# IR_Sync_Emitter_with_sensor.net
KiCad netlist of a schematic drawn in EAGLE
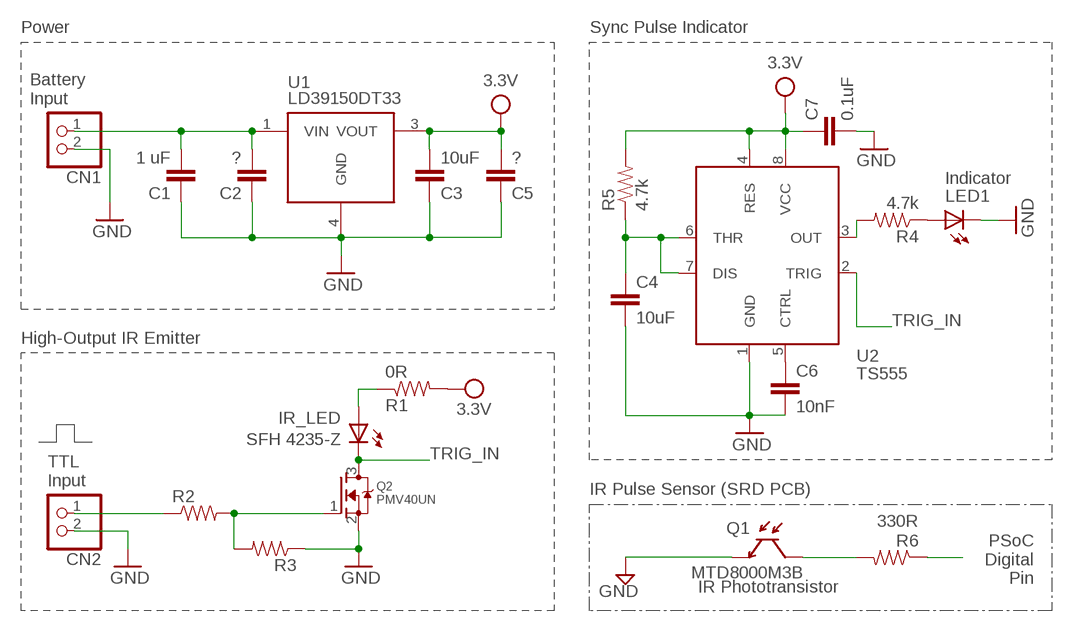
[diagram p0: schematic, sheet 1]

(export (version "E")
  (design (tool "Eeschema 10.0.6"))
  (components
    (comp (ref "C1")
      (value "1 uF")
      (footprint "eagle-import:CAPC2012X100N")
      (libsource (lib "eagle-import") (part "CC0805-N"))
    )
    (comp (ref "C2")
      (value "?")
      (footprint "eagle-import:CAPC2012X100N")
      (libsource (lib "eagle-import") (part "CC0805-N"))
    )
    (comp (ref "C3")
      (value "10uF")
      (footprint "eagle-import:CAPC2012X100N")
      (libsource (lib "eagle-import") (part "CC0805-N"))
    )
    (comp (ref "C4")
      (value "10uF")
      (footprint "eagle-import:CAPC2012X100N")
      (libsource (lib "eagle-import") (part "CC0805-N"))
    )
    (comp (ref "C5")
      (value "?")
      (footprint "eagle-import:CAPC2012X100N")
      (libsource (lib "eagle-import") (part "CC0805-N"))
    )
    (comp (ref "C6")
      (value "10nF")
      (footprint "eagle-import:CAPC2012X100N")
      (libsource (lib "eagle-import") (part "CC0805-N"))
    )
    (comp (ref "C7")
      (value "0.1uF")
      (footprint "eagle-import:CAPC2012X100N")
      (libsource (lib "eagle-import") (part "CC0805-N"))
    )
    (comp (ref "CN1")
      (value "JST_2PIN-SMT-RA")
      (footprint "eagle-import:JST-PH-2-SMT-RA")
      (libsource (lib "eagle-import") (part "JST_2PIN-SMT-RA"))
    )
    (comp (ref "CN2")
      (value "JST_2PIN-SMT-RA")
      (footprint "eagle-import:JST-PH-2-SMT-RA")
      (libsource (lib "eagle-import") (part "JST_2PIN-SMT-RA"))
    )
    (comp (ref "IR_LED")
      (value "LEDIR_SMT16.2X11.2")
      (footprint "eagle-import:LED_SMT6.2X11.2")
      (libsource (lib "eagle-import") (part "LEDIR_SMT16.2X11.2"))
    )
    (comp (ref "LED1")
      (value "LED0603")
      (footprint "eagle-import:CHIPLED_0603")
      (libsource (lib "eagle-import") (part "LED0603"))
    )
    (comp (ref "Q1")
      (value "MTD8000M3B")
      (footprint "eagle-import:MTD8000M3B-T")
      (libsource (lib "eagle-import") (part "PHOTOTRANSISTOR"))
    )
    (comp (ref "Q2")
      (value "PMV40UN")
      (footprint "eagle-import:SOT23")
      (libsource (lib "eagle-import") (part "MOSFET-NREFLOW"))
    )
    (comp (ref "R1")
      (value "0R")
      (footprint "eagle-import:RESC3116X65N")
      (libsource (lib "eagle-import") (part "RR1206-N"))
    )
    (comp (ref "R2")
      (value "RR0805-N")
      (footprint "eagle-import:RESC2012X60N")
      (libsource (lib "eagle-import") (part "RR0805-N"))
    )
    (comp (ref "R3")
      (value "RR0805-N")
      (footprint "eagle-import:RESC2012X60N")
      (libsource (lib "eagle-import") (part "RR0805-N"))
    )
    (comp (ref "R4")
      (value "4.7k")
      (footprint "eagle-import:RESC2012X60N")
      (libsource (lib "eagle-import") (part "RR0805-N"))
    )
    (comp (ref "R5")
      (value "4.7k")
      (footprint "eagle-import:RESC2012X60N")
      (libsource (lib "eagle-import") (part "RR0805-N"))
    )
    (comp (ref "R6")
      (value "330R")
      (footprint "eagle-import:RESC2012X60N")
      (libsource (lib "eagle-import") (part "RR0805-N"))
    )
    (comp (ref "U1")
      (value "LM2931_FIXED")
      (footprint "eagle-import:DPAK")
      (libsource (lib "eagle-import") (part "LM2931_FIXED"))
    )
    (comp (ref "U2")
      (value "TS555")
      (footprint "eagle-import:SO08")
      (libsource (lib "eagle-import") (part "TS555"))
    )
  )
  (nets
    (net (code "1") (name "/TRIG_IN") (class "Default")
      (node (ref "IR_LED") (pin "C") (pinfunction "C_C") (pintype "passive"))
      (node (ref "Q2") (pin "3") (pinfunction "D_3") (pintype "bidirectional"))
      (node (ref "U2") (pin "2") (pinfunction "TRIG_2") (pintype "bidirectional"))
    )
    (net (code "2") (name "GND") (class "Default")
      (node (ref "C1") (pin "1") (pinfunction "1_1") (pintype "passive"))
      (node (ref "C2") (pin "1") (pinfunction "1_1") (pintype "passive"))
      (node (ref "C3") (pin "1") (pinfunction "1_1") (pintype "passive"))
      (node (ref "C4") (pin "2") (pinfunction "2_2") (pintype "passive"))
      (node (ref "C5") (pin "1") (pinfunction "1_1") (pintype "passive"))
      (node (ref "C6") (pin "2") (pinfunction "2_2") (pintype "passive"))
      (node (ref "C7") (pin "2") (pinfunction "2_2") (pintype "passive"))
      (node (ref "CN1") (pin "2") (pinfunction "1_2") (pintype "passive"))
      (node (ref "CN2") (pin "2") (pinfunction "1_2") (pintype "passive"))
      (node (ref "LED1") (pin "C") (pinfunction "C_C") (pintype "passive"))
      (node (ref "Q1") (pin "E") (pinfunction "E_E") (pintype "bidirectional"))
      (node (ref "Q2") (pin "2") (pinfunction "S_2") (pintype "bidirectional"))
      (node (ref "R3") (pin "1") (pinfunction "1_1") (pintype "passive"))
      (node (ref "U1") (pin "4") (pinfunction "GND_4") (pintype "bidirectional"))
      (node (ref "U2") (pin "1") (pinfunction "GND_1") (pintype "power_in"))
    )
    (net (code "3") (name "Net-(CN1-2)") (class "Default")
      (node (ref "C1") (pin "2") (pinfunction "2_2") (pintype "passive"))
      (node (ref "C2") (pin "2") (pinfunction "2_2") (pintype "passive"))
      (node (ref "CN1") (pin "1") (pinfunction "2_1") (pintype "passive"))
      (node (ref "U1") (pin "1") (pinfunction "VIN_1") (pintype "bidirectional"))
    )
    (net (code "4") (name "Net-(CN2-2)") (class "Default")
      (node (ref "CN2") (pin "1") (pinfunction "2_1") (pintype "passive"))
      (node (ref "R2") (pin "1") (pinfunction "1_1") (pintype "passive"))
    )
    (net (code "5") (name "Net-(IR_LED-PadA)") (class "Default")
      (node (ref "IR_LED") (pin "A") (pinfunction "A_A") (pintype "passive"))
      (node (ref "R1") (pin "1") (pinfunction "1_1") (pintype "passive"))
    )
    (net (code "6") (name "Net-(LED1-PadA)") (class "Default")
      (node (ref "LED1") (pin "A") (pinfunction "A_A") (pintype "passive"))
      (node (ref "R4") (pin "1") (pinfunction "1_1") (pintype "passive"))
    )
    (net (code "7") (name "Net-(Q1-PadC)") (class "Default")
      (node (ref "Q1") (pin "C") (pinfunction "C_C") (pintype "bidirectional"))
      (node (ref "R6") (pin "2") (pinfunction "2_2") (pintype "passive"))
    )
    (net (code "8") (name "Net-(Q2-G)") (class "Default")
      (node (ref "Q2") (pin "1") (pinfunction "G_1") (pintype "bidirectional"))
      (node (ref "R2") (pin "2") (pinfunction "2_2") (pintype "passive"))
      (node (ref "R3") (pin "2") (pinfunction "2_2") (pintype "passive"))
    )
    (net (code "9") (name "Net-(U2-CTRL)") (class "Default")
      (node (ref "C6") (pin "1") (pinfunction "1_1") (pintype "passive"))
      (node (ref "U2") (pin "5") (pinfunction "CTRL_5") (pintype "bidirectional"))
    )
    (net (code "10") (name "Net-(U2-DIS)") (class "Default")
      (node (ref "C4") (pin "1") (pinfunction "1_1") (pintype "passive"))
      (node (ref "R5") (pin "1") (pinfunction "1_1") (pintype "passive"))
      (node (ref "U2") (pin "6") (pinfunction "THR_6") (pintype "bidirectional"))
      (node (ref "U2") (pin "7") (pinfunction "DIS_7") (pintype "bidirectional"))
    )
    (net (code "11") (name "Net-(U2-OUT)") (class "Default")
      (node (ref "R4") (pin "2") (pinfunction "2_2") (pintype "passive"))
      (node (ref "U2") (pin "3") (pinfunction "OUT_3") (pintype "output"))
    )
    (net (code "12") (name "VDD") (class "Default")
      (node (ref "C3") (pin "2") (pinfunction "2_2") (pintype "passive"))
      (node (ref "C5") (pin "2") (pinfunction "2_2") (pintype "passive"))
      (node (ref "C7") (pin "1") (pinfunction "1_1") (pintype "passive"))
      (node (ref "R1") (pin "2") (pinfunction "2_2") (pintype "passive"))
      (node (ref "R5") (pin "2") (pinfunction "2_2") (pintype "passive"))
      (node (ref "U1") (pin "3") (pinfunction "VOUT_3") (pintype "bidirectional"))
      (node (ref "U2") (pin "4") (pinfunction "RES_4") (pintype "bidirectional"))
      (node (ref "U2") (pin "8") (pinfunction "VCC_8") (pintype "power_in"))
    )
    (net (code "13") (name "unconnected-(R6-Pad1)") (class "Default")
      (node (ref "R6") (pin "1") (pinfunction "1_1") (pintype "passive"))
    )
  )
)
